# design.net
KiCad netlist of a schematic drawn in Altium Designer
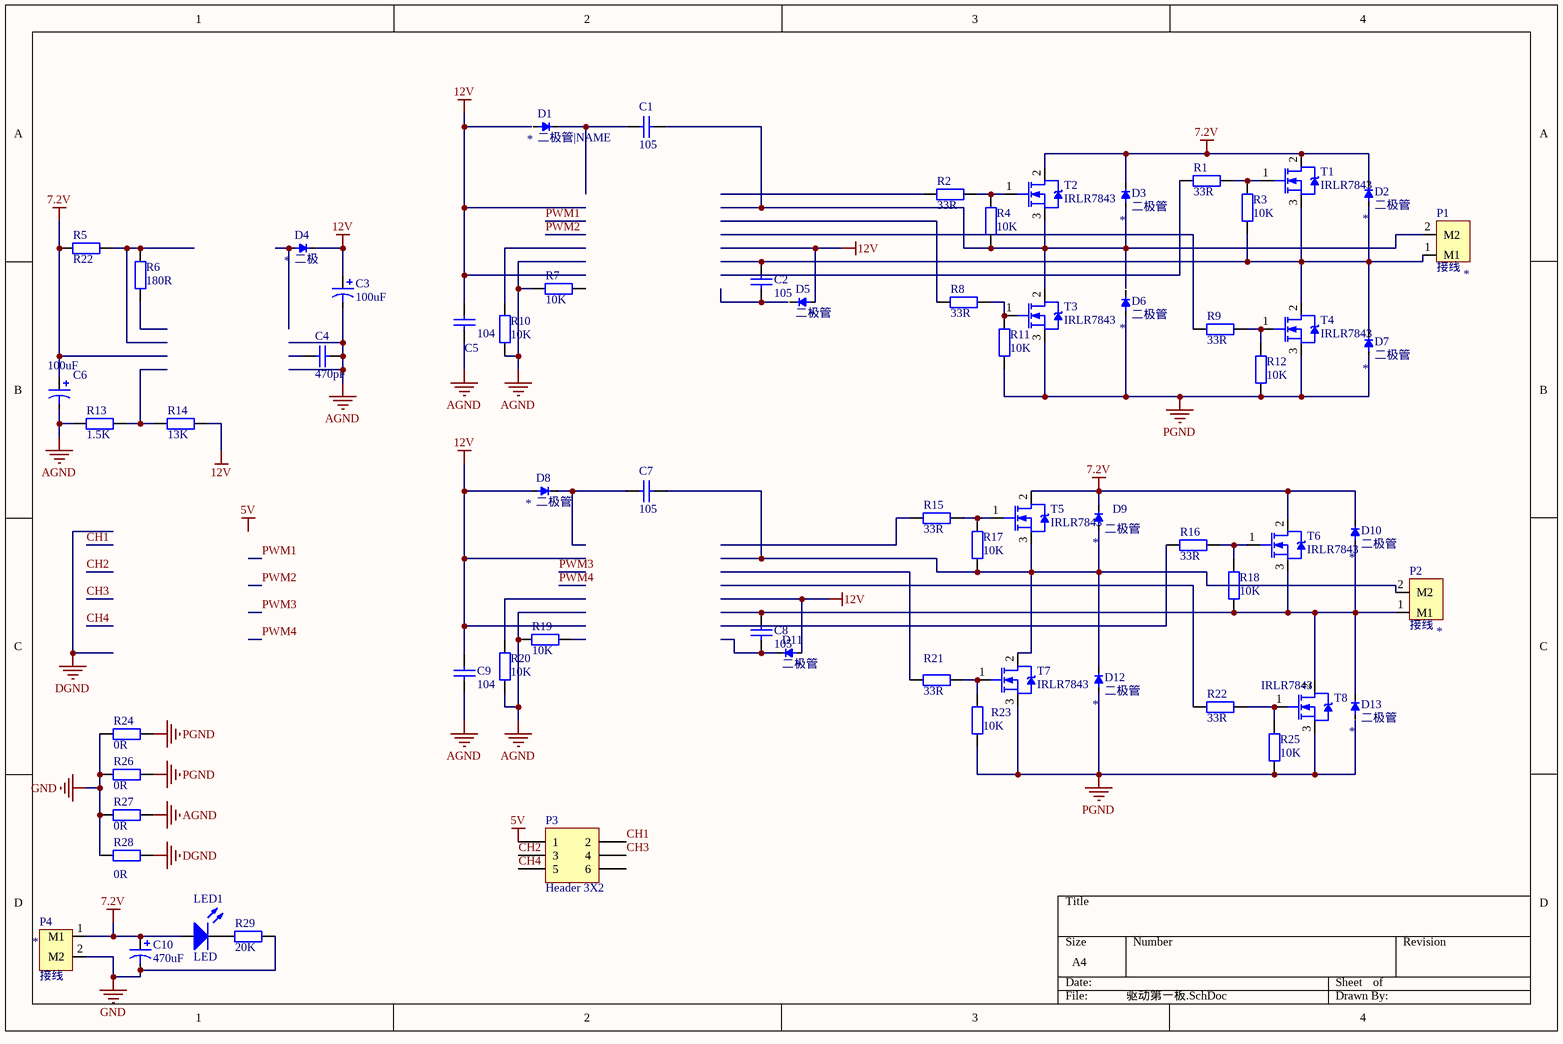
[diagram p0: 驱动第一板.SchDoc]

(export (version "E")
  (design (tool "Eeschema 10.0.6"))
  (components
    (comp (ref "C1")
      (value "105")
      (footprint "0805")
      (description "无极电容")
      (libsource (lib "JMU智能车专用2.0.8") (part "Cap"))
    )
    (comp (ref "C2")
      (value "105")
      (footprint "0805")
      (description "无极电容")
      (libsource (lib "JMU智能车专用2.0.8") (part "Cap"))
    )
    (comp (ref "C3")
      (value "100uF")
      (footprint "ED6.3")
      (description "ED8:470UF  ED6.3:100UF")
      (libsource (lib "JMU智能车专用2.0.8") (part "固态贴片电容"))
    )
    (comp (ref "C4")
      (value "470pF")
      (footprint "0603")
      (description "无极电容")
      (libsource (lib "JMU智能车专用2.0.8") (part "Cap"))
    )
    (comp (ref "C5")
      (value "104")
      (footprint "0805")
      (description "无极电容")
      (libsource (lib "JMU智能车专用2.0.8") (part "Cap"))
    )
    (comp (ref "C6")
      (value "100uF")
      (footprint "Pol Cap(220uF)")
      (description "通用有极电容")
      (libsource (lib "JMU智能车专用2.0.8") (part "pol cap"))
    )
    (comp (ref "C7")
      (value "105")
      (footprint "0805")
      (description "无极电容")
      (libsource (lib "JMU智能车专用2.0.8") (part "Cap"))
    )
    (comp (ref "C8")
      (value "105")
      (footprint "0805")
      (description "无极电容")
      (libsource (lib "JMU智能车专用2.0.8") (part "Cap"))
    )
    (comp (ref "C9")
      (value "104")
      (footprint "0805")
      (description "无极电容")
      (libsource (lib "JMU智能车专用2.0.8") (part "Cap"))
    )
    (comp (ref "C10")
      (value "470uF")
      (footprint "ED8")
      (description "ED8:470UF  ED6.3:100UF")
      (libsource (lib "JMU智能车专用2.0.8") (part "固态贴片电容"))
    )
    (comp (ref "D1")
      (value "*")
      (footprint "二极管")
      (fields (field (name "ALTIUM_UNNAMED_2") "二极管"))
      (libsource (lib "JMU智能车专用2.0.8") (part "二极管"))
    )
    (comp (ref "D2")
      (value "*")
      (footprint "二极管")
      (fields (field (name "C") "二极管"))
      (libsource (lib "JMU智能车专用2.0.8") (part "二极管"))
    )
    (comp (ref "D3")
      (value "*")
      (footprint "二极管")
      (fields (field (name "C") "二极管"))
      (libsource (lib "JMU智能车专用2.0.8") (part "二极管"))
    )
    (comp (ref "D4")
      (value "*")
      (footprint "二极管")
      (fields (field (name "ALTIUM_UNNAMED_2") "二极"))
      (libsource (lib "JMU智能车专用2.0.8") (part "二极管"))
    )
    (comp (ref "D5")
      (value "*")
      (footprint "二极管")
      (fields (field (name "C") "二极管"))
      (libsource (lib "JMU智能车专用2.0.8") (part "二极管"))
    )
    (comp (ref "D6")
      (value "*")
      (footprint "二极管")
      (fields (field (name "C") "二极管"))
      (libsource (lib "JMU智能车专用2.0.8") (part "二极管"))
    )
    (comp (ref "D7")
      (value "*")
      (footprint "二极管")
      (fields (field (name "C") "二极管"))
      (libsource (lib "JMU智能车专用2.0.8") (part "二极管"))
    )
    (comp (ref "D8")
      (value "*")
      (footprint "二极管")
      (fields (field (name "C") "二极管"))
      (libsource (lib "JMU智能车专用2.0.8") (part "二极管"))
    )
    (comp (ref "D9")
      (value "*")
      (footprint "二极管")
      (fields (field (name "C") "二极管"))
      (libsource (lib "JMU智能车专用2.0.8") (part "二极管"))
    )
    (comp (ref "D10")
      (value "*")
      (footprint "二极管")
      (fields (field (name "C") "二极管"))
      (libsource (lib "JMU智能车专用2.0.8") (part "二极管"))
    )
    (comp (ref "D11")
      (value "*")
      (footprint "二极管")
      (fields (field (name "C") "二极管"))
      (libsource (lib "JMU智能车专用2.0.8") (part "二极管"))
    )
    (comp (ref "D12")
      (value "*")
      (footprint "二极管")
      (fields (field (name "C") "二极管"))
      (libsource (lib "JMU智能车专用2.0.8") (part "二极管"))
    )
    (comp (ref "D13")
      (value "*")
      (footprint "二极管")
      (fields (field (name "C") "二极管"))
      (libsource (lib "JMU智能车专用2.0.8") (part "二极管"))
    )
    (comp (ref "LED1")
      (value "LED")
      (footprint "LED(0805)")
      (description "发光二极管")
      (libsource (lib "JMU智能车专用2.0.8") (part "LED"))
    )
    (comp (ref "P1")
      (value "*")
      (footprint "接线端子")
      (fields (field (name "ALTIUM_UNNAMED_3") "接线"))
      (libsource (lib "JMU智能车专用2.0.8") (part "接线端子"))
    )
    (comp (ref "P2")
      (value "*")
      (footprint "接线端子")
      (fields (field (name "ALTIUM_UNNAMED_3") "接线"))
      (libsource (lib "JMU智能车专用2.0.8") (part "接线端子"))
    )
    (comp (ref "P3")
      (value "Header 3X2")
      (footprint "HDR2X3")
      (description "Header, 3-Pin, Dual row")
      (fields (field (name "PUBLISHER") "Altium Limited"))
      (libsource (lib "Miscellaneous Connectors") (part "Header 3X2"))
    )
    (comp (ref "P4")
      (value "*")
      (footprint "接线端子")
      (fields (field (name "ALTIUM_UNNAMED_3") "接线"))
      (libsource (lib "") (part "接线端子_1"))
    )
    (comp (ref "R1")
      (value "33R")
      (footprint "0603")
      (description "通用电阻")
      (libsource (lib "") (part "Res_2"))
    )
    (comp (ref "R2")
      (value "33R")
      (footprint "0603")
      (description "通用电阻")
      (libsource (lib "JMU智能车专用2.0.8") (part "Res"))
    )
    (comp (ref "R3")
      (value "10K")
      (footprint "0603")
      (description "通用电阻")
      (libsource (lib "") (part "Res_1"))
    )
    (comp (ref "R4")
      (value "10K")
      (footprint "0603")
      (description "通用电阻")
      (libsource (lib "") (part "Res_1"))
    )
    (comp (ref "R5")
      (value "R22")
      (footprint "0603")
      (description "通用电阻")
      (libsource (lib "JMU智能车专用2.0.8") (part "Res"))
    )
    (comp (ref "R6")
      (value "180R")
      (footprint "0603")
      (description "通用电阻")
      (libsource (lib "") (part "Res_1"))
    )
    (comp (ref "R7")
      (value "10K")
      (footprint "0603")
      (description "通用电阻")
      (libsource (lib "JMU智能车专用2.0.8") (part "Res"))
    )
    (comp (ref "R8")
      (value "33R")
      (footprint "0603")
      (description "通用电阻")
      (libsource (lib "JMU智能车专用2.0.8") (part "Res"))
    )
    (comp (ref "R9")
      (value "33R")
      (footprint "0603")
      (description "通用电阻")
      (libsource (lib "") (part "Res_2"))
    )
    (comp (ref "R10")
      (value "10K")
      (footprint "0603")
      (description "通用电阻")
      (libsource (lib "") (part "Res_1"))
    )
    (comp (ref "R11")
      (value "10K")
      (footprint "0603")
      (description "通用电阻")
      (libsource (lib "") (part "Res_1"))
    )
    (comp (ref "R12")
      (value "10K")
      (footprint "0603")
      (description "通用电阻")
      (libsource (lib "") (part "Res_3"))
    )
    (comp (ref "R13")
      (value "1.5K")
      (footprint "0603")
      (description "通用电阻")
      (libsource (lib "JMU智能车专用2.0.8") (part "Res"))
    )
    (comp (ref "R14")
      (value "13K")
      (footprint "0603")
      (description "通用电阻")
      (libsource (lib "JMU智能车专用2.0.8") (part "Res"))
    )
    (comp (ref "R15")
      (value "33R")
      (footprint "0603")
      (description "通用电阻")
      (libsource (lib "JMU智能车专用2.0.8") (part "Res"))
    )
    (comp (ref "R16")
      (value "33R")
      (footprint "0603")
      (description "通用电阻")
      (libsource (lib "JMU智能车专用2.0.8") (part "Res"))
    )
    (comp (ref "R17")
      (value "10K")
      (footprint "0603")
      (description "通用电阻")
      (libsource (lib "") (part "Res_1"))
    )
    (comp (ref "R18")
      (value "10K")
      (footprint "0603")
      (description "通用电阻")
      (libsource (lib "") (part "Res_1"))
    )
    (comp (ref "R19")
      (value "10K")
      (footprint "0603")
      (description "通用电阻")
      (libsource (lib "") (part "Res_2"))
    )
    (comp (ref "R20")
      (value "10K")
      (footprint "0603")
      (description "通用电阻")
      (libsource (lib "") (part "Res_1"))
    )
    (comp (ref "R21")
      (value "33R")
      (footprint "0603")
      (description "通用电阻")
      (libsource (lib "JMU智能车专用2.0.8") (part "Res"))
    )
    (comp (ref "R22")
      (value "33R")
      (footprint "0603")
      (description "通用电阻")
      (libsource (lib "JMU智能车专用2.0.8") (part "Res"))
    )
    (comp (ref "R23")
      (value "10K")
      (footprint "0603")
      (description "通用电阻")
      (libsource (lib "") (part "Res_1"))
    )
    (comp (ref "R24")
      (value "0R")
      (footprint "0805")
      (description "通用电阻")
      (libsource (lib "JMU智能车专用2.0.8") (part "Res"))
    )
    (comp (ref "R25")
      (value "10K")
      (footprint "0603")
      (description "通用电阻")
      (libsource (lib "") (part "Res_1"))
    )
    (comp (ref "R26")
      (value "0R")
      (footprint "0805")
      (description "通用电阻")
      (libsource (lib "JMU智能车专用2.0.8") (part "Res"))
    )
    (comp (ref "R27")
      (value "0R")
      (footprint "0805")
      (description "通用电阻")
      (libsource (lib "JMU智能车专用2.0.8") (part "Res"))
    )
    (comp (ref "R28")
      (value "0R")
      (footprint "0805")
      (description "通用电阻")
      (libsource (lib "JMU智能车专用2.0.8") (part "Res"))
    )
    (comp (ref "R29")
      (value "20K")
      (footprint "0603")
      (description "通用电阻")
      (libsource (lib "JMU智能车专用2.0.8") (part "Res"))
    )
    (comp (ref "T1")
      (value "IRLR7843")
      (footprint "IRLR7843(MOS)")
      (libsource (lib "JMU智能车专用2.0.8") (part "N_MOS(IRLR7843)"))
    )
    (comp (ref "T2")
      (value "IRLR7843")
      (footprint "IRLR7843(MOS)")
      (libsource (lib "JMU智能车专用2.0.8") (part "N_MOS(IRLR7843)"))
    )
    (comp (ref "T3")
      (value "IRLR7843")
      (footprint "IRLR7843(MOS)")
      (libsource (lib "JMU智能车专用2.0.8") (part "N_MOS(IRLR7843)"))
    )
    (comp (ref "T4")
      (value "IRLR7843")
      (footprint "IRLR7843(MOS)")
      (libsource (lib "JMU智能车专用2.0.8") (part "N_MOS(IRLR7843)"))
    )
    (comp (ref "T5")
      (value "IRLR7843")
      (footprint "IRLR7843(MOS)")
      (libsource (lib "JMU智能车专用2.0.8") (part "N_MOS(IRLR7843)"))
    )
    (comp (ref "T6")
      (value "IRLR7843")
      (footprint "IRLR7843(MOS)")
      (libsource (lib "JMU智能车专用2.0.8") (part "N_MOS(IRLR7843)"))
    )
    (comp (ref "T7")
      (value "IRLR7843")
      (footprint "IRLR7843(MOS)")
      (libsource (lib "JMU智能车专用2.0.8") (part "N_MOS(IRLR7843)"))
    )
    (comp (ref "T8")
      (value "IRLR7843")
      (footprint "IRLR7843(MOS)")
      (libsource (lib "JMU智能车专用2.0.8") (part "N_MOS(IRLR7843)"))
    )
  )
  (nets
    (net (code "1") (name "/CH1") (class "Default")
      (node (ref "P3") (pin "2") (pinfunction "2_2") (pintype "passive"))
    )
    (net (code "2") (name "/CH2") (class "Default")
      (node (ref "P3") (pin "3") (pinfunction "3_3") (pintype "passive"))
    )
    (net (code "3") (name "/CH3") (class "Default")
      (node (ref "P3") (pin "4") (pinfunction "4_4") (pintype "passive"))
    )
    (net (code "4") (name "/CH4") (class "Default")
      (node (ref "P3") (pin "5") (pinfunction "5_5") (pintype "passive"))
    )
    (net (code "9") (name "5V") (class "Default")
      (node (ref "P3") (pin "1") (pinfunction "1_1") (pintype "passive"))
    )
    (net (code "10") (name "7.2V") (class "Default")
      (node (ref "C10") (pin "1") (pinfunction "1_1") (pintype "passive"))
      (node (ref "C6") (pin "1") (pinfunction "1_1") (pintype "passive"))
      (node (ref "D10") (pin "2") (pinfunction "-_2") (pintype "passive"))
      (node (ref "D2") (pin "2") (pinfunction "-_2") (pintype "passive"))
      (node (ref "D3") (pin "2") (pinfunction "-_2") (pintype "passive"))
      (node (ref "D9") (pin "2") (pinfunction "-_2") (pintype "passive"))
      (node (ref "LED1") (pin "1") (pinfunction "A_1") (pintype "passive"))
      (node (ref "P4") (pin "1") (pinfunction "M1_1") (pintype "passive"))
      (node (ref "R5") (pin "1") (pinfunction "1_1") (pintype "passive"))
      (node (ref "T1") (pin "2") (pinfunction "D_2") (pintype "passive"))
      (node (ref "T2") (pin "2") (pinfunction "D_2") (pintype "passive"))
      (node (ref "T5") (pin "2") (pinfunction "D_2") (pintype "passive"))
      (node (ref "T6") (pin "2") (pinfunction "D_2") (pintype "passive"))
    )
    (net (code "11") (name "12V") (class "Default")
      (node (ref "C3") (pin "1") (pinfunction "1_1") (pintype "passive"))
      (node (ref "C5") (pin "2") (pinfunction "2_2") (pintype "passive"))
      (node (ref "C9") (pin "2") (pinfunction "2_2") (pintype "passive"))
      (node (ref "D11") (pin "1") (pinfunction "+_1") (pintype "passive"))
      (node (ref "D4") (pin "2") (pinfunction "-_2") (pintype "passive"))
      (node (ref "D5") (pin "1") (pinfunction "+_1") (pintype "passive"))
      (node (ref "D8") (pin "1") (pinfunction "+_1") (pintype "passive"))
      (node (ref "R14") (pin "2") (pinfunction "2_2") (pintype "passive"))
    )
    (net (code "12") (name "AGND") (class "Default")
      (node (ref "C3") (pin "2") (pinfunction "2_2") (pintype "passive"))
      (node (ref "C4") (pin "2") (pinfunction "2_2") (pintype "passive"))
      (node (ref "C5") (pin "1") (pinfunction "1_1") (pintype "passive"))
      (node (ref "C6") (pin "2") (pinfunction "2_2") (pintype "passive"))
      (node (ref "C9") (pin "1") (pinfunction "1_1") (pintype "passive"))
      (node (ref "R10") (pin "1") (pinfunction "1_1") (pintype "passive"))
      (node (ref "R13") (pin "1") (pinfunction "1_1") (pintype "passive"))
      (node (ref "R19") (pin "2") (pinfunction "2_2") (pintype "passive"))
      (node (ref "R20") (pin "1") (pinfunction "1_1") (pintype "passive"))
      (node (ref "R27") (pin "2") (pinfunction "2_2") (pintype "passive"))
      (node (ref "R7") (pin "1") (pinfunction "1_1") (pintype "passive"))
    )
    (net (code "13") (name "DGND") (class "Default")
      (node (ref "R28") (pin "2") (pinfunction "2_2") (pintype "passive"))
    )
    (net (code "14") (name "GND") (class "Default")
      (node (ref "C10") (pin "2") (pinfunction "2_2") (pintype "passive"))
      (node (ref "P4") (pin "2") (pinfunction "M2_2") (pintype "passive"))
      (node (ref "R24") (pin "1") (pinfunction "1_1") (pintype "passive"))
      (node (ref "R26") (pin "1") (pinfunction "1_1") (pintype "passive"))
      (node (ref "R27") (pin "1") (pinfunction "1_1") (pintype "passive"))
      (node (ref "R28") (pin "1") (pinfunction "1_1") (pintype "passive"))
      (node (ref "R29") (pin "2") (pinfunction "2_2") (pintype "passive"))
    )
    (net (code "15") (name "Net-(D1--)") (class "Default")
      (node (ref "C1") (pin "1") (pinfunction "1_1") (pintype "passive"))
      (node (ref "D1") (pin "2") (pinfunction "-_2") (pintype "passive"))
    )
    (net (code "16") (name "Net-(D2-+)") (class "Default")
      (node (ref "C2") (pin "2") (pinfunction "2_2") (pintype "passive"))
      (node (ref "D2") (pin "1") (pinfunction "+_1") (pintype "passive"))
      (node (ref "D7") (pin "2") (pinfunction "-_2") (pintype "passive"))
      (node (ref "P1") (pin "1") (pinfunction "M1_1") (pintype "passive"))
      (node (ref "R3") (pin "1") (pinfunction "1_1") (pintype "passive"))
      (node (ref "T1") (pin "3") (pinfunction "S_3") (pintype "passive"))
      (node (ref "T4") (pin "2") (pinfunction "D_2") (pintype "passive"))
    )
    (net (code "17") (name "Net-(D3-+)") (class "Default")
      (node (ref "C1") (pin "2") (pinfunction "2_2") (pintype "passive"))
      (node (ref "D3") (pin "1") (pinfunction "+_1") (pintype "passive"))
      (node (ref "P1") (pin "2") (pinfunction "M2_2") (pintype "passive"))
      (node (ref "R4") (pin "1") (pinfunction "1_1") (pintype "passive"))
      (node (ref "T2") (pin "3") (pinfunction "S_3") (pintype "passive"))
      (node (ref "T3") (pin "2") (pinfunction "D_2") (pintype "passive"))
    )
    (net (code "18") (name "Net-(D8--)") (class "Default")
      (node (ref "C7") (pin "1") (pinfunction "1_1") (pintype "passive"))
      (node (ref "D8") (pin "2") (pinfunction "-_2") (pintype "passive"))
    )
    (net (code "19") (name "Net-(D10-+)") (class "Default")
      (node (ref "C8") (pin "2") (pinfunction "2_2") (pintype "passive"))
      (node (ref "D10") (pin "1") (pinfunction "+_1") (pintype "passive"))
      (node (ref "D13") (pin "2") (pinfunction "-_2") (pintype "passive"))
      (node (ref "P2") (pin "1") (pinfunction "M1_1") (pintype "passive"))
      (node (ref "R18") (pin "1") (pinfunction "1_1") (pintype "passive"))
      (node (ref "T6") (pin "3") (pinfunction "S_3") (pintype "passive"))
      (node (ref "T8") (pin "2") (pinfunction "D_2") (pintype "passive"))
    )
    (net (code "20") (name "Net-(D11--)") (class "Default")
      (node (ref "C8") (pin "1") (pinfunction "1_1") (pintype "passive"))
      (node (ref "D11") (pin "2") (pinfunction "-_2") (pintype "passive"))
    )
    (net (code "21") (name "Net-(D12--)") (class "Default")
      (node (ref "C7") (pin "2") (pinfunction "2_2") (pintype "passive"))
      (node (ref "D12") (pin "2") (pinfunction "-_2") (pintype "passive"))
      (node (ref "D9") (pin "1") (pinfunction "+_1") (pintype "passive"))
      (node (ref "P2") (pin "2") (pinfunction "M2_2") (pintype "passive"))
      (node (ref "R17") (pin "1") (pinfunction "1_1") (pintype "passive"))
      (node (ref "T5") (pin "3") (pinfunction "S_3") (pintype "passive"))
      (node (ref "T7") (pin "2") (pinfunction "D_2") (pintype "passive"))
    )
    (net (code "22") (name "Net-(LED1-K)") (class "Default")
      (node (ref "LED1") (pin "2") (pinfunction "K_2") (pintype "passive"))
      (node (ref "R29") (pin "1") (pinfunction "1_1") (pintype "passive"))
    )
    (net (code "23") (name "Net-(R5-Pad2)") (class "Default")
      (node (ref "R5") (pin "2") (pinfunction "2_2") (pintype "passive"))
      (node (ref "R6") (pin "2") (pinfunction "2_2") (pintype "passive"))
    )
    (net (code "24") (name "Net-(R13-Pad2)") (class "Default")
      (node (ref "R13") (pin "2") (pinfunction "2_2") (pintype "passive"))
      (node (ref "R14") (pin "1") (pinfunction "1_1") (pintype "passive"))
    )
    (net (code "25") (name "Net-(T1-G)") (class "Default")
      (node (ref "R1") (pin "1") (pinfunction "1_1") (pintype "passive"))
      (node (ref "R3") (pin "2") (pinfunction "2_2") (pintype "passive"))
      (node (ref "T1") (pin "1") (pinfunction "G_1") (pintype "passive"))
    )
    (net (code "26") (name "Net-(T2-G)") (class "Default")
      (node (ref "R2") (pin "2") (pinfunction "2_2") (pintype "passive"))
      (node (ref "R4") (pin "2") (pinfunction "2_2") (pintype "passive"))
      (node (ref "T2") (pin "1") (pinfunction "G_1") (pintype "passive"))
    )
    (net (code "27") (name "Net-(T3-G)") (class "Default")
      (node (ref "R11") (pin "2") (pinfunction "2_2") (pintype "passive"))
      (node (ref "R8") (pin "2") (pinfunction "2_2") (pintype "passive"))
      (node (ref "T3") (pin "1") (pinfunction "G_1") (pintype "passive"))
    )
    (net (code "28") (name "Net-(T4-G)") (class "Default")
      (node (ref "R12") (pin "1") (pinfunction "1_1") (pintype "passive"))
      (node (ref "R9") (pin "1") (pinfunction "1_1") (pintype "passive"))
      (node (ref "T4") (pin "1") (pinfunction "G_1") (pintype "passive"))
    )
    (net (code "29") (name "Net-(T5-G)") (class "Default")
      (node (ref "R15") (pin "2") (pinfunction "2_2") (pintype "passive"))
      (node (ref "R17") (pin "2") (pinfunction "2_2") (pintype "passive"))
      (node (ref "T5") (pin "1") (pinfunction "G_1") (pintype "passive"))
    )
    (net (code "30") (name "Net-(T6-G)") (class "Default")
      (node (ref "R16") (pin "2") (pinfunction "2_2") (pintype "passive"))
      (node (ref "R18") (pin "2") (pinfunction "2_2") (pintype "passive"))
      (node (ref "T6") (pin "1") (pinfunction "G_1") (pintype "passive"))
    )
    (net (code "31") (name "Net-(T7-G)") (class "Default")
      (node (ref "R21") (pin "2") (pinfunction "2_2") (pintype "passive"))
      (node (ref "R23") (pin "2") (pinfunction "2_2") (pintype "passive"))
      (node (ref "T7") (pin "1") (pinfunction "G_1") (pintype "passive"))
    )
    (net (code "32") (name "Net-(T8-G)") (class "Default")
      (node (ref "R22") (pin "2") (pinfunction "2_2") (pintype "passive"))
      (node (ref "R25") (pin "2") (pinfunction "2_2") (pintype "passive"))
      (node (ref "T8") (pin "1") (pinfunction "G_1") (pintype "passive"))
    )
    (net (code "33") (name "PGND") (class "Default")
      (node (ref "D12") (pin "1") (pinfunction "+_1") (pintype "passive"))
      (node (ref "D6") (pin "1") (pinfunction "+_1") (pintype "passive"))
      (node (ref "D7") (pin "1") (pinfunction "+_1") (pintype "passive"))
      (node (ref "R11") (pin "1") (pinfunction "1_1") (pintype "passive"))
      (node (ref "R12") (pin "2") (pinfunction "2_2") (pintype "passive"))
      (node (ref "R23") (pin "1") (pinfunction "1_1") (pintype "passive"))
      (node (ref "R24") (pin "2") (pinfunction "2_2") (pintype "passive"))
      (node (ref "R25") (pin "1") (pinfunction "1_1") (pintype "passive"))
      (node (ref "R26") (pin "2") (pinfunction "2_2") (pintype "passive"))
      (node (ref "T3") (pin "3") (pinfunction "S_3") (pintype "passive"))
      (node (ref "T4") (pin "3") (pinfunction "S_3") (pintype "passive"))
      (node (ref "T7") (pin "3") (pinfunction "S_3") (pintype "passive"))
      (node (ref "T8") (pin "3") (pinfunction "S_3") (pintype "passive"))
    )
    (net (code "34") (name "unconnected-(C2-Pad1)") (class "Default")
      (node (ref "C2") (pin "1") (pinfunction "1_1") (pintype "passive"))
    )
    (net (code "35") (name "unconnected-(C4-Pad1)") (class "Default")
      (node (ref "C4") (pin "1") (pinfunction "1_1") (pintype "passive"))
    )
    (net (code "36") (name "unconnected-(D1-+-Pad1)") (class "Default")
      (node (ref "D1") (pin "1") (pinfunction "+_1") (pintype "passive"))
    )
    (net (code "37") (name "unconnected-(D4-+-Pad1)") (class "Default")
      (node (ref "D4") (pin "1") (pinfunction "+_1") (pintype "passive"))
    )
    (net (code "38") (name "unconnected-(D5---Pad2)") (class "Default")
      (node (ref "D5") (pin "2") (pinfunction "-_2") (pintype "passive"))
    )
    (net (code "39") (name "unconnected-(D6---Pad2)") (class "Default")
      (node (ref "D6") (pin "2") (pinfunction "-_2") (pintype "passive"))
    )
    (net (code "40") (name "unconnected-(D13-+-Pad1)") (class "Default")
      (node (ref "D13") (pin "1") (pinfunction "+_1") (pintype "passive"))
    )
    (net (code "41") (name "unconnected-(P3-Pad6)") (class "Default")
      (node (ref "P3") (pin "6") (pinfunction "6_6") (pintype "passive"))
    )
    (net (code "42") (name "unconnected-(R1-Pad2)") (class "Default")
      (node (ref "R1") (pin "2") (pinfunction "2_2") (pintype "passive"))
    )
    (net (code "43") (name "unconnected-(R2-Pad1)") (class "Default")
      (node (ref "R2") (pin "1") (pinfunction "1_1") (pintype "passive"))
    )
    (net (code "44") (name "unconnected-(R6-Pad1)") (class "Default")
      (node (ref "R6") (pin "1") (pinfunction "1_1") (pintype "passive"))
    )
    (net (code "45") (name "unconnected-(R7-Pad2)") (class "Default")
      (node (ref "R7") (pin "2") (pinfunction "2_2") (pintype "passive"))
    )
    (net (code "46") (name "unconnected-(R8-Pad1)") (class "Default")
      (node (ref "R8") (pin "1") (pinfunction "1_1") (pintype "passive"))
    )
    (net (code "47") (name "unconnected-(R9-Pad2)") (class "Default")
      (node (ref "R9") (pin "2") (pinfunction "2_2") (pintype "passive"))
    )
    (net (code "48") (name "unconnected-(R10-Pad2)") (class "Default")
      (node (ref "R10") (pin "2") (pinfunction "2_2") (pintype "passive"))
    )
    (net (code "49") (name "unconnected-(R15-Pad1)") (class "Default")
      (node (ref "R15") (pin "1") (pinfunction "1_1") (pintype "passive"))
    )
    (net (code "50") (name "unconnected-(R16-Pad1)") (class "Default")
      (node (ref "R16") (pin "1") (pinfunction "1_1") (pintype "passive"))
    )
    (net (code "51") (name "unconnected-(R19-Pad1)") (class "Default")
      (node (ref "R19") (pin "1") (pinfunction "1_1") (pintype "passive"))
    )
    (net (code "52") (name "unconnected-(R20-Pad2)") (class "Default")
      (node (ref "R20") (pin "2") (pinfunction "2_2") (pintype "passive"))
    )
    (net (code "53") (name "unconnected-(R21-Pad1)") (class "Default")
      (node (ref "R21") (pin "1") (pinfunction "1_1") (pintype "passive"))
    )
    (net (code "54") (name "unconnected-(R22-Pad1)") (class "Default")
      (node (ref "R22") (pin "1") (pinfunction "1_1") (pintype "passive"))
    )
  )
)
